# gatedriver_trafo_sma_compact_ACDC_ultra.net
KiCad netlist of a schematic drawn in EAGLE
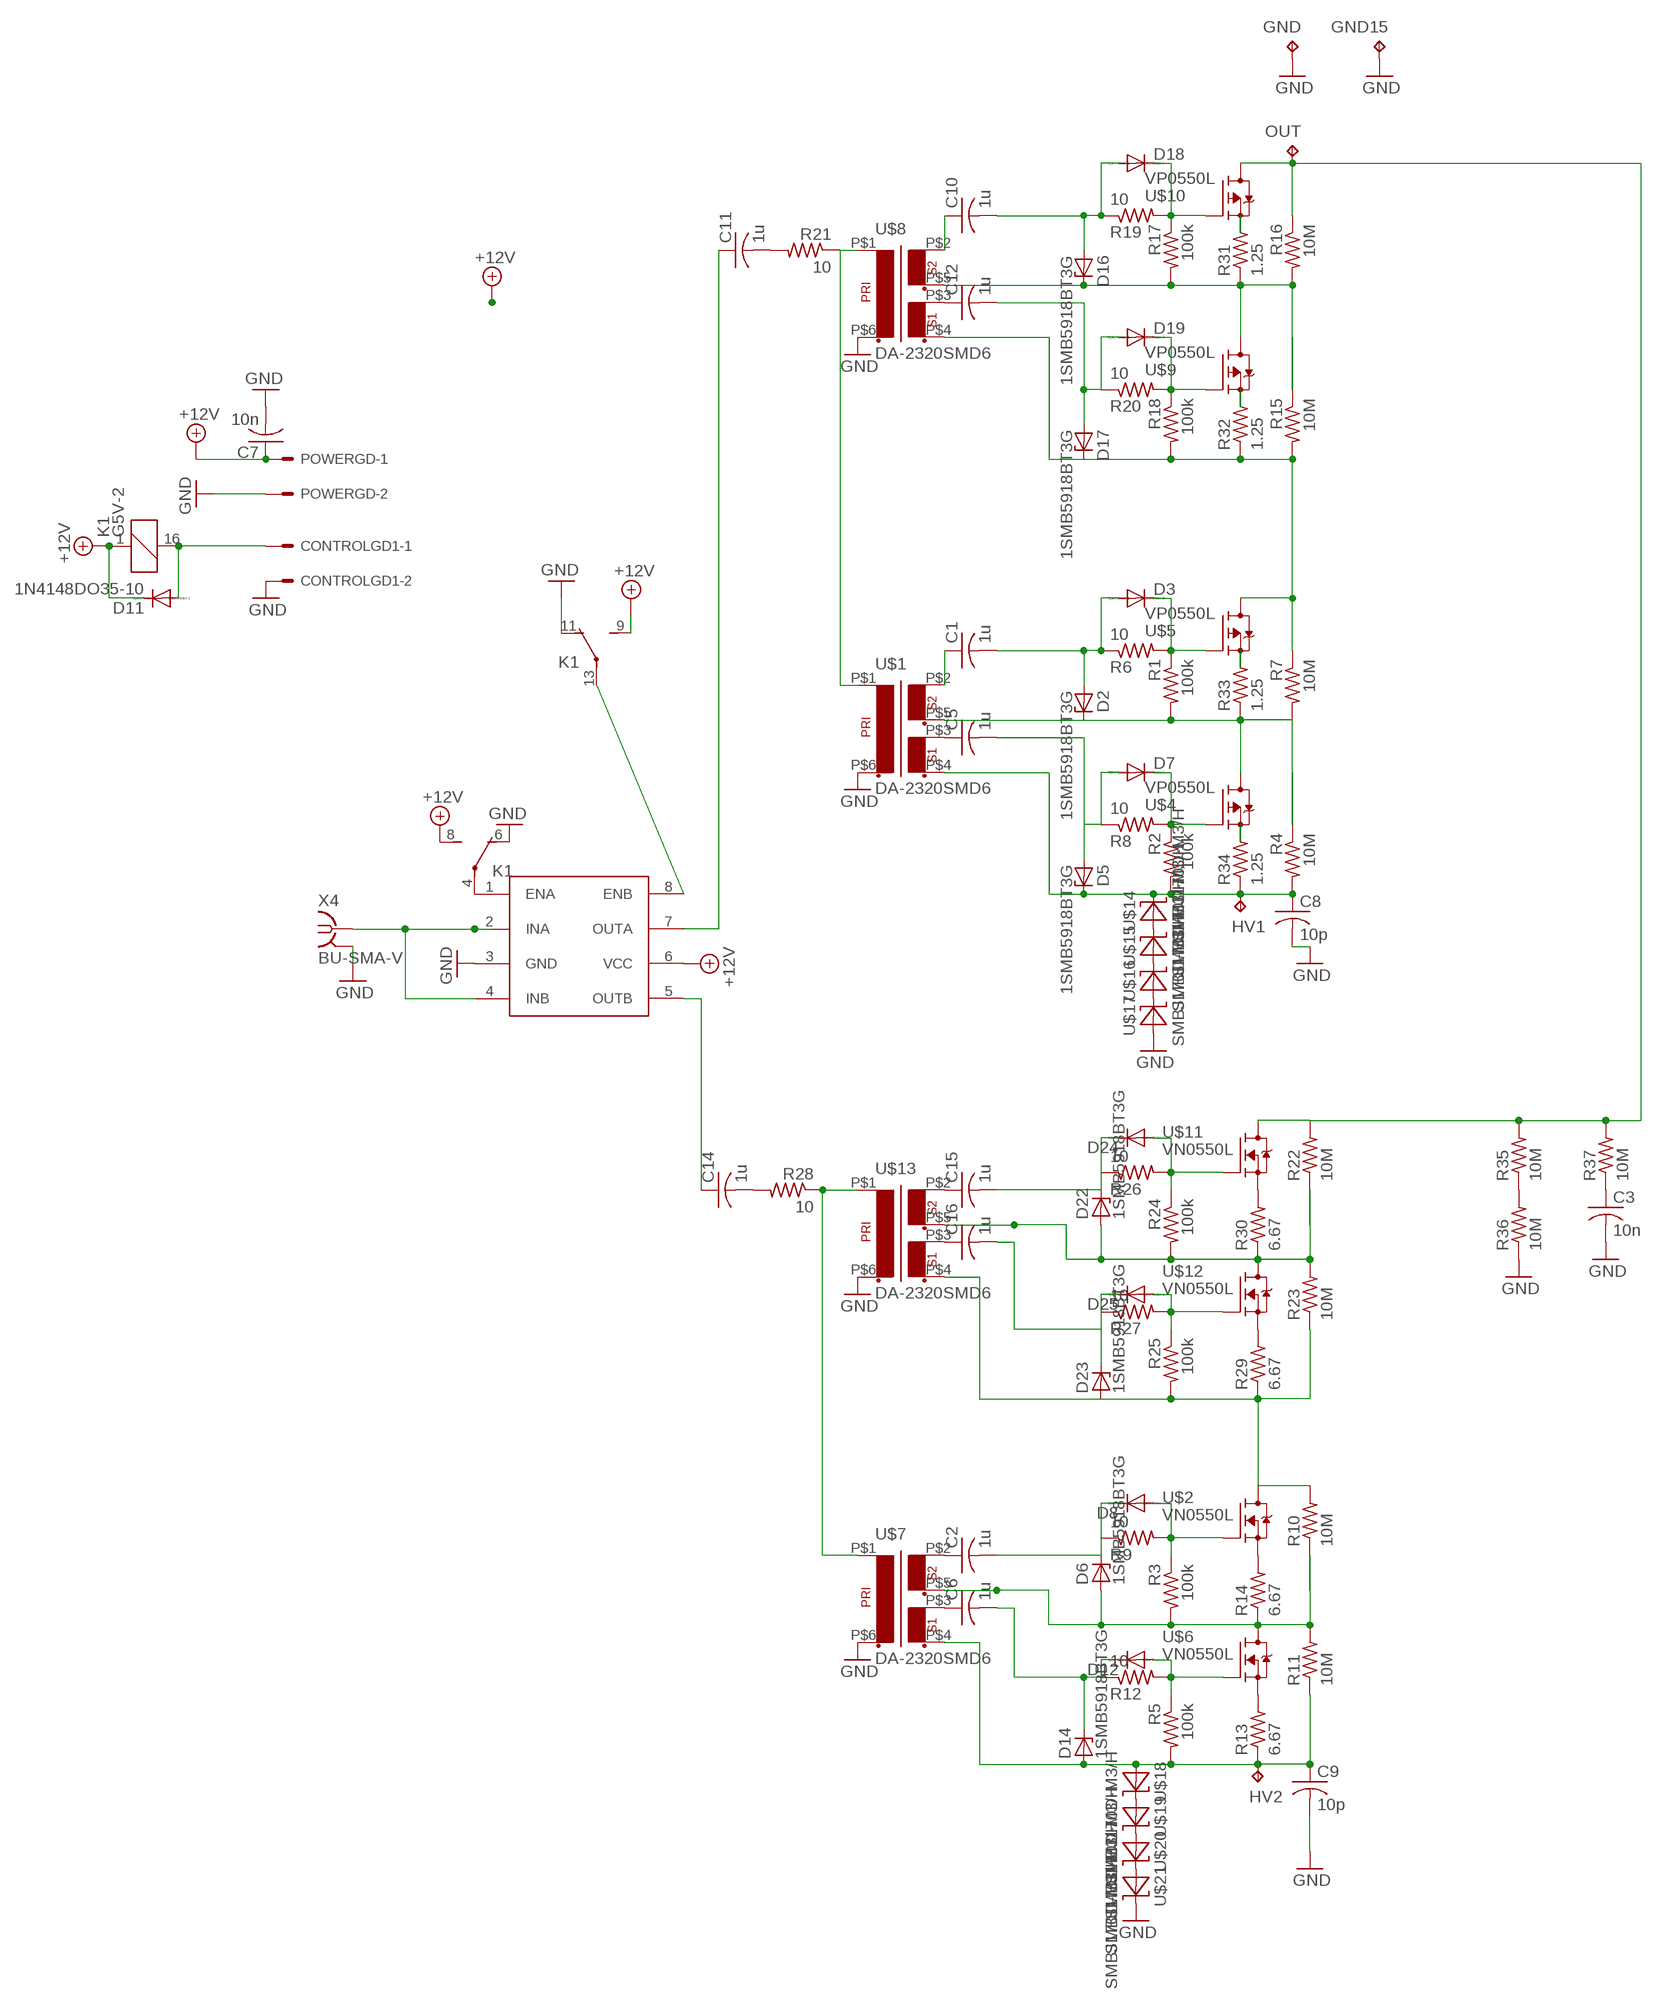
[diagram p0: schematic, sheet 1]

(export (version "E")
  (design (tool "Eeschema 10.0.6"))
  (components
    (comp (ref "C1")
      (value "1u")
      (footprint "eagle-import:C0805")
      (libsource (lib "eagle-import") (part "resistor_C-USC0805"))
    )
    (comp (ref "C2")
      (value "1u")
      (footprint "eagle-import:C0805")
      (libsource (lib "eagle-import") (part "resistor_C-USC0805"))
    )
    (comp (ref "C3")
      (value "10n")
      (footprint "eagle-import:C0805")
      (libsource (lib "eagle-import") (part "resistor_C-USC0805"))
    )
    (comp (ref "C5")
      (value "1u")
      (footprint "eagle-import:C0805")
      (libsource (lib "eagle-import") (part "resistor_C-USC0805"))
    )
    (comp (ref "C6")
      (value "1u")
      (footprint "eagle-import:C0805")
      (libsource (lib "eagle-import") (part "resistor_C-USC0805"))
    )
    (comp (ref "C7")
      (value "10n")
      (footprint "eagle-import:C050-030X075")
      (libsource (lib "eagle-import") (part "C-US050-030X075"))
    )
    (comp (ref "C8")
      (value "10p")
      (footprint "eagle-import:C102-064X133")
      (libsource (lib "eagle-import") (part "resistor_C-US102-064X133"))
    )
    (comp (ref "C9")
      (value "10p")
      (footprint "eagle-import:C102-064X133")
      (libsource (lib "eagle-import") (part "resistor_C-US102-064X133"))
    )
    (comp (ref "C10")
      (value "1u")
      (footprint "eagle-import:C0805")
      (libsource (lib "eagle-import") (part "resistor_C-USC0805"))
    )
    (comp (ref "C11")
      (value "1u")
      (footprint "eagle-import:C0805")
      (libsource (lib "eagle-import") (part "resistor_C-USC0805"))
    )
    (comp (ref "C12")
      (value "1u")
      (footprint "eagle-import:C0805")
      (libsource (lib "eagle-import") (part "resistor_C-USC0805"))
    )
    (comp (ref "C14")
      (value "1u")
      (footprint "eagle-import:C0805")
      (libsource (lib "eagle-import") (part "resistor_C-USC0805"))
    )
    (comp (ref "C15")
      (value "1u")
      (footprint "eagle-import:C0805")
      (libsource (lib "eagle-import") (part "resistor_C-USC0805"))
    )
    (comp (ref "C16")
      (value "1u")
      (footprint "eagle-import:C0805")
      (libsource (lib "eagle-import") (part "resistor_C-USC0805"))
    )
    (comp (ref "CONTROLGD1")
      (value "KK-156-2")
      (footprint "eagle-import:KK-156-2")
      (libsource (lib "eagle-import") (part "KK-156-2"))
    )
    (comp (ref "D2")
      (value "1SMB5918BT3G")
      (footprint "eagle-import:SMB")
      (libsource (lib "eagle-import") (part "ZENER-DIODESMB"))
    )
    (comp (ref "D3")
      (value "DIODE-SMB")
      (footprint "eagle-import:SMB")
      (libsource (lib "eagle-import") (part "DIODE-SMB"))
    )
    (comp (ref "D5")
      (value "1SMB5918BT3G")
      (footprint "eagle-import:SMB")
      (libsource (lib "eagle-import") (part "ZENER-DIODESMB"))
    )
    (comp (ref "D6")
      (value "1SMB5918BT3G")
      (footprint "eagle-import:SMB")
      (libsource (lib "eagle-import") (part "ZENER-DIODESMB"))
    )
    (comp (ref "D7")
      (value "DIODE-SMB")
      (footprint "eagle-import:SMB")
      (libsource (lib "eagle-import") (part "DIODE-SMB"))
    )
    (comp (ref "D8")
      (value "DIODE-SMB")
      (footprint "eagle-import:SMB")
      (libsource (lib "eagle-import") (part "DIODE-SMB"))
    )
    (comp (ref "D11")
      (value "1N4148DO35-10")
      (footprint "eagle-import:DO35-10")
      (libsource (lib "eagle-import") (part "1N4148DO35-10"))
    )
    (comp (ref "D12")
      (value "DIODE-SMB")
      (footprint "eagle-import:SMB")
      (libsource (lib "eagle-import") (part "DIODE-SMB"))
    )
    (comp (ref "D14")
      (value "1SMB5918BT3G")
      (footprint "eagle-import:SMB")
      (libsource (lib "eagle-import") (part "ZENER-DIODESMB"))
    )
    (comp (ref "D16")
      (value "1SMB5918BT3G")
      (footprint "eagle-import:SMB")
      (libsource (lib "eagle-import") (part "ZENER-DIODESMB"))
    )
    (comp (ref "D17")
      (value "1SMB5918BT3G")
      (footprint "eagle-import:SMB")
      (libsource (lib "eagle-import") (part "ZENER-DIODESMB"))
    )
    (comp (ref "D18")
      (value "DIODE-SMB")
      (footprint "eagle-import:SMB")
      (libsource (lib "eagle-import") (part "DIODE-SMB"))
    )
    (comp (ref "D19")
      (value "DIODE-SMB")
      (footprint "eagle-import:SMB")
      (libsource (lib "eagle-import") (part "DIODE-SMB"))
    )
    (comp (ref "D22")
      (value "1SMB5918BT3G")
      (footprint "eagle-import:SMB")
      (libsource (lib "eagle-import") (part "ZENER-DIODESMB"))
    )
    (comp (ref "D23")
      (value "1SMB5918BT3G")
      (footprint "eagle-import:SMB")
      (libsource (lib "eagle-import") (part "ZENER-DIODESMB"))
    )
    (comp (ref "D24")
      (value "DIODE-SMB")
      (footprint "eagle-import:SMB")
      (libsource (lib "eagle-import") (part "DIODE-SMB"))
    )
    (comp (ref "D25")
      (value "DIODE-SMB")
      (footprint "eagle-import:SMB")
      (libsource (lib "eagle-import") (part "DIODE-SMB"))
    )
    (comp (ref "GND")
      (value "TPPAD1-20Y")
      (footprint "eagle-import:P1-20Y")
      (libsource (lib "eagle-import") (part "TPPAD1-20Y"))
    )
    (comp (ref "GND15")
      (value "TPPAD1-20Y")
      (footprint "eagle-import:P1-20Y")
      (libsource (lib "eagle-import") (part "TPPAD1-20Y"))
    )
    (comp (ref "HV1")
      (value "TPPAD1-20Y")
      (footprint "eagle-import:P1-20Y")
      (libsource (lib "eagle-import") (part "TPPAD1-20Y"))
    )
    (comp (ref "HV2")
      (value "TPPAD1-20Y")
      (footprint "eagle-import:P1-20Y")
      (libsource (lib "eagle-import") (part "TPPAD1-20Y"))
    )
    (comp (ref "K1")
      (value "G5V-2")
      (footprint "eagle-import:G5V-2")
      (fields (field (name "MPN") "G5V-2 5DC"))
      (libsource (lib "eagle-import") (part "G5V-2"))
    )
    (comp (ref "OUT")
      (value "TPPAD1-20Y")
      (footprint "eagle-import:P1-20Y")
      (libsource (lib "eagle-import") (part "TPPAD1-20Y"))
    )
    (comp (ref "POWERGD")
      (value "KK-156-2")
      (footprint "eagle-import:KK-156-2")
      (libsource (lib "eagle-import") (part "KK-156-2"))
    )
    (comp (ref "R1")
      (value "100k")
      (footprint "eagle-import:R0805")
      (libsource (lib "eagle-import") (part "R-US_R0805"))
    )
    (comp (ref "R2")
      (value "100k")
      (footprint "eagle-import:R0805")
      (libsource (lib "eagle-import") (part "R-US_R0805"))
    )
    (comp (ref "R3")
      (value "100k")
      (footprint "eagle-import:R0805")
      (libsource (lib "eagle-import") (part "R-US_R0805"))
    )
    (comp (ref "R4")
      (value "10M")
      (footprint "eagle-import:R2512")
      (libsource (lib "eagle-import") (part "R-US_R2512"))
    )
    (comp (ref "R5")
      (value "100k")
      (footprint "eagle-import:R0805")
      (libsource (lib "eagle-import") (part "R-US_R0805"))
    )
    (comp (ref "R6")
      (value "10")
      (footprint "eagle-import:R0805")
      (libsource (lib "eagle-import") (part "R-US_R0805"))
    )
    (comp (ref "R7")
      (value "10M")
      (footprint "eagle-import:R2512")
      (libsource (lib "eagle-import") (part "R-US_R2512"))
    )
    (comp (ref "R8")
      (value "10")
      (footprint "eagle-import:R0805")
      (libsource (lib "eagle-import") (part "R-US_R0805"))
    )
    (comp (ref "R9")
      (value "10")
      (footprint "eagle-import:R0805")
      (libsource (lib "eagle-import") (part "R-US_R0805"))
    )
    (comp (ref "R10")
      (value "10M")
      (footprint "eagle-import:R2512")
      (libsource (lib "eagle-import") (part "R-US_R2512"))
    )
    (comp (ref "R11")
      (value "10M")
      (footprint "eagle-import:R2512")
      (libsource (lib "eagle-import") (part "R-US_R2512"))
    )
    (comp (ref "R12")
      (value "10")
      (footprint "eagle-import:R0805")
      (libsource (lib "eagle-import") (part "R-US_R0805"))
    )
    (comp (ref "R13")
      (value "6.67")
      (footprint "eagle-import:R0805")
      (libsource (lib "eagle-import") (part "R-US_R0805"))
    )
    (comp (ref "R14")
      (value "6.67")
      (footprint "eagle-import:R0805")
      (libsource (lib "eagle-import") (part "R-US_R0805"))
    )
    (comp (ref "R15")
      (value "10M")
      (footprint "eagle-import:R2512")
      (libsource (lib "eagle-import") (part "R-US_R2512"))
    )
    (comp (ref "R16")
      (value "10M")
      (footprint "eagle-import:R2512")
      (libsource (lib "eagle-import") (part "R-US_R2512"))
    )
    (comp (ref "R17")
      (value "100k")
      (footprint "eagle-import:R0805")
      (libsource (lib "eagle-import") (part "R-US_R0805"))
    )
    (comp (ref "R18")
      (value "100k")
      (footprint "eagle-import:R0805")
      (libsource (lib "eagle-import") (part "R-US_R0805"))
    )
    (comp (ref "R19")
      (value "10")
      (footprint "eagle-import:R0805")
      (libsource (lib "eagle-import") (part "R-US_R0805"))
    )
    (comp (ref "R20")
      (value "10")
      (footprint "eagle-import:R0805")
      (libsource (lib "eagle-import") (part "R-US_R0805"))
    )
    (comp (ref "R21")
      (value "10")
      (footprint "eagle-import:R0805")
      (libsource (lib "eagle-import") (part "R-US_R0805"))
    )
    (comp (ref "R22")
      (value "10M")
      (footprint "eagle-import:R2512")
      (libsource (lib "eagle-import") (part "R-US_R2512"))
    )
    (comp (ref "R23")
      (value "10M")
      (footprint "eagle-import:R2512")
      (libsource (lib "eagle-import") (part "R-US_R2512"))
    )
    (comp (ref "R24")
      (value "100k")
      (footprint "eagle-import:R0805")
      (libsource (lib "eagle-import") (part "R-US_R0805"))
    )
    (comp (ref "R25")
      (value "100k")
      (footprint "eagle-import:R0805")
      (libsource (lib "eagle-import") (part "R-US_R0805"))
    )
    (comp (ref "R26")
      (value "10")
      (footprint "eagle-import:R0805")
      (libsource (lib "eagle-import") (part "R-US_R0805"))
    )
    (comp (ref "R27")
      (value "10")
      (footprint "eagle-import:R0805")
      (libsource (lib "eagle-import") (part "R-US_R0805"))
    )
    (comp (ref "R28")
      (value "10")
      (footprint "eagle-import:R0805")
      (libsource (lib "eagle-import") (part "R-US_R0805"))
    )
    (comp (ref "R29")
      (value "6.67")
      (footprint "eagle-import:R0805")
      (libsource (lib "eagle-import") (part "R-US_R0805"))
    )
    (comp (ref "R30")
      (value "6.67")
      (footprint "eagle-import:R0805")
      (libsource (lib "eagle-import") (part "R-US_R0805"))
    )
    (comp (ref "R31")
      (value "1.25")
      (footprint "eagle-import:R0805")
      (libsource (lib "eagle-import") (part "R-US_R0805"))
    )
    (comp (ref "R32")
      (value "1.25")
      (footprint "eagle-import:R0805")
      (libsource (lib "eagle-import") (part "R-US_R0805"))
    )
    (comp (ref "R33")
      (value "1.25")
      (footprint "eagle-import:R0805")
      (libsource (lib "eagle-import") (part "R-US_R0805"))
    )
    (comp (ref "R34")
      (value "1.25")
      (footprint "eagle-import:R0805")
      (libsource (lib "eagle-import") (part "R-US_R0805"))
    )
    (comp (ref "R35")
      (value "10M")
      (footprint "eagle-import:R2512")
      (libsource (lib "eagle-import") (part "R-US_R2512"))
    )
    (comp (ref "R36")
      (value "10M")
      (footprint "eagle-import:R2512")
      (libsource (lib "eagle-import") (part "R-US_R2512"))
    )
    (comp (ref "R37")
      (value "10M")
      (footprint "eagle-import:R2512")
      (libsource (lib "eagle-import") (part "R-US_R2512"))
    )
    (comp (ref "U$1")
      (value "DA-2320SMD6")
      (footprint "eagle-import:SMD6")
      (libsource (lib "eagle-import") (part "DA-2320SMD6"))
    )
    (comp (ref "U$2")
      (value "VN0550L")
      (footprint "eagle-import:TO92L")
      (libsource (lib "eagle-import") (part "VN0550L"))
    )
    (comp (ref "U$3")
      (value "UCC27425")
      (footprint "eagle-import:DIL08")
      (libsource (lib "eagle-import") (part "UCC27425"))
    )
    (comp (ref "U$4")
      (value "VP0550L")
      (footprint "eagle-import:TO92L")
      (libsource (lib "eagle-import") (part "VP0550L"))
    )
    (comp (ref "U$5")
      (value "VP0550L")
      (footprint "eagle-import:TO92L")
      (libsource (lib "eagle-import") (part "VP0550L"))
    )
    (comp (ref "U$6")
      (value "VN0550L")
      (footprint "eagle-import:TO92L")
      (libsource (lib "eagle-import") (part "VN0550L"))
    )
    (comp (ref "U$7")
      (value "DA-2320SMD6")
      (footprint "eagle-import:SMD6")
      (libsource (lib "eagle-import") (part "DA-2320SMD6"))
    )
    (comp (ref "U$8")
      (value "DA-2320SMD6")
      (footprint "eagle-import:SMD6")
      (libsource (lib "eagle-import") (part "DA-2320SMD6"))
    )
    (comp (ref "U$9")
      (value "VP0550L")
      (footprint "eagle-import:TO92L")
      (libsource (lib "eagle-import") (part "VP0550L"))
    )
    (comp (ref "U$10")
      (value "VP0550L")
      (footprint "eagle-import:TO92L")
      (libsource (lib "eagle-import") (part "VP0550L"))
    )
    (comp (ref "U$11")
      (value "VN0550L")
      (footprint "eagle-import:TO92L")
      (libsource (lib "eagle-import") (part "VN0550L"))
    )
    (comp (ref "U$12")
      (value "VN0550L")
      (footprint "eagle-import:TO92L")
      (libsource (lib "eagle-import") (part "VN0550L"))
    )
    (comp (ref "U$13")
      (value "DA-2320SMD6")
      (footprint "eagle-import:SMD6")
      (libsource (lib "eagle-import") (part "DA-2320SMD6"))
    )
    (comp (ref "U$14")
      (value "SMBJ170D-M3/H")
      (footprint "eagle-import:DO214AA")
      (libsource (lib "eagle-import") (part "SMBJ170D-M3/H"))
    )
    (comp (ref "U$15")
      (value "SMBJ170D-M3/H")
      (footprint "eagle-import:DO214AA")
      (libsource (lib "eagle-import") (part "SMBJ170D-M3/H"))
    )
    (comp (ref "U$16")
      (value "SMBJ170D-M3/H")
      (footprint "eagle-import:DO214AA")
      (libsource (lib "eagle-import") (part "SMBJ170D-M3/H"))
    )
    (comp (ref "U$17")
      (value "SMBJ170D-M3/H")
      (footprint "eagle-import:DO214AA")
      (libsource (lib "eagle-import") (part "SMBJ170D-M3/H"))
    )
    (comp (ref "U$18")
      (value "SMBJ170D-M3/H")
      (footprint "eagle-import:DO214AA")
      (libsource (lib "eagle-import") (part "SMBJ170D-M3/H"))
    )
    (comp (ref "U$19")
      (value "SMBJ170D-M3/H")
      (footprint "eagle-import:DO214AA")
      (libsource (lib "eagle-import") (part "SMBJ170D-M3/H"))
    )
    (comp (ref "U$20")
      (value "SMBJ170D-M3/H")
      (footprint "eagle-import:DO214AA")
      (libsource (lib "eagle-import") (part "SMBJ170D-M3/H"))
    )
    (comp (ref "U$21")
      (value "SMBJ170D-M3/H")
      (footprint "eagle-import:DO214AA")
      (libsource (lib "eagle-import") (part "SMBJ170D-M3/H"))
    )
    (comp (ref "X4")
      (value "BU-SMA-V")
      (footprint "eagle-import:BU-SMA-V")
      (libsource (lib "eagle-import") (part "BU-SMA-V"))
    )
  )
  (nets
    (net (code "1") (name "+12V") (class "Default")
      (node (ref "C7") (pin "1") (pinfunction "1_1") (pintype "passive"))
      (node (ref "D11") (pin "C") (pinfunction "C_C") (pintype "passive"))
      (node (ref "K1") (pin "1") (pinfunction "1_1") (pintype "passive"))
      (node (ref "K1") (pin "8") (pinfunction "S_8") (pintype "passive"))
      (node (ref "K1") (pin "9") (pinfunction "S_9") (pintype "passive"))
      (node (ref "POWERGD") (pin "1") (pinfunction "S_1") (pintype "passive"))
      (node (ref "U$3") (pin "6") (pinfunction "VCC_6") (pintype "bidirectional"))
    )
    (net (code "2") (name "GND") (class "Default")
      (node (ref "C3") (pin "2") (pinfunction "2_2") (pintype "passive"))
      (node (ref "C7") (pin "2") (pinfunction "2_2") (pintype "passive"))
      (node (ref "C8") (pin "2") (pinfunction "2_2") (pintype "passive"))
      (node (ref "C9") (pin "2") (pinfunction "2_2") (pintype "passive"))
      (node (ref "CONTROLGD1") (pin "2") (pinfunction "S_2") (pintype "passive"))
      (node (ref "GND") (pin "TP") (pinfunction "TP_TP") (pintype "input"))
      (node (ref "GND15") (pin "TP") (pinfunction "TP_TP") (pintype "input"))
      (node (ref "K1") (pin "11") (pinfunction "O_11") (pintype "passive"))
      (node (ref "K1") (pin "6") (pinfunction "O_6") (pintype "passive"))
      (node (ref "POWERGD") (pin "2") (pinfunction "S_2") (pintype "passive"))
      (node (ref "R36") (pin "1") (pinfunction "1_1") (pintype "passive"))
      (node (ref "U$1") (pin "P$6") (pinfunction "2_P$6") (pintype "passive"))
      (node (ref "U$13") (pin "P$6") (pinfunction "2_P$6") (pintype "passive"))
      (node (ref "U$17") (pin "A") (pinfunction "A_A") (pintype "passive"))
      (node (ref "U$21") (pin "C") (pinfunction "C_C") (pintype "passive"))
      (node (ref "U$3") (pin "3") (pinfunction "GND_3") (pintype "bidirectional"))
      (node (ref "U$7") (pin "P$6") (pinfunction "2_P$6") (pintype "passive"))
      (node (ref "U$8") (pin "P$6") (pinfunction "2_P$6") (pintype "passive"))
      (node (ref "X4") (pin "2") (pinfunction "2_2") (pintype "passive"))
      (node (ref "X4") (pin "3") (pinfunction "2_3") (pintype "passive"))
      (node (ref "X4") (pin "4") (pinfunction "2_4") (pintype "passive"))
      (node (ref "X4") (pin "5") (pinfunction "2_5") (pintype "passive"))
    )
    (net (code "3") (name "Net-(C1-Pad2)") (class "Default")
      (node (ref "C1") (pin "2") (pinfunction "2_2") (pintype "passive"))
      (node (ref "D2") (pin "A") (pinfunction "A_A") (pintype "passive"))
      (node (ref "D3") (pin "A") (pinfunction "A_A") (pintype "passive"))
      (node (ref "R6") (pin "1") (pinfunction "1_1") (pintype "passive"))
    )
    (net (code "4") (name "Net-(C2-Pad2)") (class "Default")
      (node (ref "C2") (pin "2") (pinfunction "2_2") (pintype "passive"))
      (node (ref "D6") (pin "C") (pinfunction "C_C") (pintype "passive"))
      (node (ref "D8") (pin "C") (pinfunction "C_C") (pintype "passive"))
      (node (ref "R9") (pin "1") (pinfunction "1_1") (pintype "passive"))
    )
    (net (code "5") (name "Net-(C3-Pad1)") (class "Default")
      (node (ref "C3") (pin "1") (pinfunction "1_1") (pintype "passive"))
      (node (ref "R37") (pin "1") (pinfunction "1_1") (pintype "passive"))
    )
    (net (code "6") (name "Net-(C5-Pad2)") (class "Default")
      (node (ref "C5") (pin "2") (pinfunction "2_2") (pintype "passive"))
      (node (ref "D5") (pin "A") (pinfunction "A_A") (pintype "passive"))
      (node (ref "D7") (pin "A") (pinfunction "A_A") (pintype "passive"))
      (node (ref "R8") (pin "1") (pinfunction "1_1") (pintype "passive"))
    )
    (net (code "7") (name "Net-(C6-Pad2)") (class "Default")
      (node (ref "C6") (pin "2") (pinfunction "2_2") (pintype "passive"))
      (node (ref "D12") (pin "C") (pinfunction "C_C") (pintype "passive"))
      (node (ref "D14") (pin "C") (pinfunction "C_C") (pintype "passive"))
      (node (ref "R12") (pin "1") (pinfunction "1_1") (pintype "passive"))
    )
    (net (code "8") (name "Net-(C10-Pad2)") (class "Default")
      (node (ref "C10") (pin "2") (pinfunction "2_2") (pintype "passive"))
      (node (ref "D16") (pin "A") (pinfunction "A_A") (pintype "passive"))
      (node (ref "D18") (pin "A") (pinfunction "A_A") (pintype "passive"))
      (node (ref "R19") (pin "1") (pinfunction "1_1") (pintype "passive"))
    )
    (net (code "9") (name "Net-(C11-Pad2)") (class "Default")
      (node (ref "C11") (pin "2") (pinfunction "2_2") (pintype "passive"))
      (node (ref "R21") (pin "2") (pinfunction "2_2") (pintype "passive"))
    )
    (net (code "10") (name "Net-(C12-Pad2)") (class "Default")
      (node (ref "C12") (pin "2") (pinfunction "2_2") (pintype "passive"))
      (node (ref "D17") (pin "A") (pinfunction "A_A") (pintype "passive"))
      (node (ref "D19") (pin "A") (pinfunction "A_A") (pintype "passive"))
      (node (ref "R20") (pin "1") (pinfunction "1_1") (pintype "passive"))
    )
    (net (code "11") (name "Net-(C14-Pad2)") (class "Default")
      (node (ref "C14") (pin "2") (pinfunction "2_2") (pintype "passive"))
      (node (ref "R28") (pin "2") (pinfunction "2_2") (pintype "passive"))
    )
    (net (code "12") (name "Net-(C15-Pad2)") (class "Default")
      (node (ref "C15") (pin "2") (pinfunction "2_2") (pintype "passive"))
      (node (ref "D22") (pin "C") (pinfunction "C_C") (pintype "passive"))
      (node (ref "D24") (pin "C") (pinfunction "C_C") (pintype "passive"))
      (node (ref "R26") (pin "1") (pinfunction "1_1") (pintype "passive"))
    )
    (net (code "13") (name "Net-(C16-Pad2)") (class "Default")
      (node (ref "C16") (pin "2") (pinfunction "2_2") (pintype "passive"))
      (node (ref "D23") (pin "C") (pinfunction "C_C") (pintype "passive"))
      (node (ref "D25") (pin "C") (pinfunction "C_C") (pintype "passive"))
      (node (ref "R27") (pin "1") (pinfunction "1_1") (pintype "passive"))
    )
    (net (code "14") (name "Net-(CONTROLGD1A-S)") (class "Default")
      (node (ref "CONTROLGD1") (pin "1") (pinfunction "S_1") (pintype "passive"))
      (node (ref "D11") (pin "A") (pinfunction "A_A") (pintype "passive"))
      (node (ref "K1") (pin "16") (pinfunction "2_16") (pintype "passive"))
    )
    (net (code "15") (name "Net-(K1A-P)") (class "Default")
      (node (ref "K1") (pin "4") (pinfunction "P_4") (pintype "passive"))
      (node (ref "U$3") (pin "1") (pinfunction "ENA_1") (pintype "bidirectional"))
    )
    (net (code "16") (name "Net-(K1B-P)") (class "Default")
      (node (ref "K1") (pin "13") (pinfunction "P_13") (pintype "passive"))
      (node (ref "U$3") (pin "8") (pinfunction "ENB_8") (pintype "bidirectional"))
    )
    (net (code "17") (name "Net-(R35-Pad1)") (class "Default")
      (node (ref "R35") (pin "1") (pinfunction "1_1") (pintype "passive"))
      (node (ref "R36") (pin "2") (pinfunction "2_2") (pintype "passive"))
    )
    (net (code "18") (name "Net-(U$1-1)") (class "Default")
      (node (ref "R21") (pin "1") (pinfunction "1_1") (pintype "passive"))
      (node (ref "U$1") (pin "P$1") (pinfunction "1_P$1") (pintype "passive"))
      (node (ref "U$8") (pin "P$1") (pinfunction "1_P$1") (pintype "passive"))
    )
    (net (code "19") (name "Net-(U$1-3)") (class "Default")
      (node (ref "C8") (pin "1") (pinfunction "1_1") (pintype "passive"))
      (node (ref "D5") (pin "C") (pinfunction "C_C") (pintype "passive"))
      (node (ref "HV1") (pin "TP") (pinfunction "TP_TP") (pintype "input"))
      (node (ref "R2") (pin "2") (pinfunction "2_2") (pintype "passive"))
      (node (ref "R34") (pin "1") (pinfunction "1_1") (pintype "passive"))
      (node (ref "R4") (pin "2") (pinfunction "2_2") (pintype "passive"))
      (node (ref "U$1") (pin "P$4") (pinfunction "3_P$4") (pintype "passive"))
      (node (ref "U$14") (pin "C") (pinfunction "C_C") (pintype "passive"))
    )
    (net (code "20") (name "Net-(U$1-4)") (class "Default")
      (node (ref "C5") (pin "1") (pinfunction "1_1") (pintype "passive"))
      (node (ref "U$1") (pin "P$3") (pinfunction "4_P$3") (pintype "passive"))
    )
    (net (code "21") (name "Net-(U$1-5)") (class "Default")
      (node (ref "D2") (pin "C") (pinfunction "C_C") (pintype "passive"))
      (node (ref "R1") (pin "2") (pinfunction "2_2") (pintype "passive"))
      (node (ref "R33") (pin "1") (pinfunction "1_1") (pintype "passive"))
      (node (ref "R4") (pin "1") (pinfunction "1_1") (pintype "passive"))
      (node (ref "R7") (pin "2") (pinfunction "2_2") (pintype "passive"))
      (node (ref "U$1") (pin "P$5") (pinfunction "5_P$5") (pintype "passive"))
      (node (ref "U$4") (pin "1") (pinfunction "D_1") (pintype "passive"))
    )
    (net (code "22") (name "Net-(U$1-6)") (class "Default")
      (node (ref "C1") (pin "1") (pinfunction "1_1") (pintype "passive"))
      (node (ref "U$1") (pin "P$2") (pinfunction "6_P$2") (pintype "passive"))
    )
    (net (code "23") (name "Net-(U$2-G)") (class "Default")
      (node (ref "D8") (pin "A") (pinfunction "A_A") (pintype "passive"))
      (node (ref "R3") (pin "1") (pinfunction "1_1") (pintype "passive"))
      (node (ref "R9") (pin "2") (pinfunction "2_2") (pintype "passive"))
      (node (ref "U$2") (pin "2") (pinfunction "G_2") (pintype "passive"))
    )
    (net (code "24") (name "Net-(U$2-S)") (class "Default")
      (node (ref "R14") (pin "2") (pinfunction "2_2") (pintype "passive"))
      (node (ref "U$2") (pin "3") (pinfunction "S_3") (pintype "passive"))
    )
    (net (code "25") (name "Net-(U$3-INA)") (class "Default")
      (node (ref "U$3") (pin "2") (pinfunction "INA_2") (pintype "bidirectional"))
      (node (ref "U$3") (pin "4") (pinfunction "INB_4") (pintype "bidirectional"))
      (node (ref "X4") (pin "1") (pinfunction "1_1") (pintype "passive"))
    )
    (net (code "26") (name "Net-(U$3-OUTA)") (class "Default")
      (node (ref "C11") (pin "1") (pinfunction "1_1") (pintype "passive"))
      (node (ref "U$3") (pin "7") (pinfunction "OUTA_7") (pintype "bidirectional"))
    )
    (net (code "27") (name "Net-(U$3-OUTB)") (class "Default")
      (node (ref "C14") (pin "1") (pinfunction "1_1") (pintype "passive"))
      (node (ref "U$3") (pin "5") (pinfunction "OUTB_5") (pintype "bidirectional"))
    )
    (net (code "28") (name "Net-(U$4-G)") (class "Default")
      (node (ref "D7") (pin "C") (pinfunction "C_C") (pintype "passive"))
      (node (ref "R2") (pin "1") (pinfunction "1_1") (pintype "passive"))
      (node (ref "R8") (pin "2") (pinfunction "2_2") (pintype "passive"))
      (node (ref "U$4") (pin "2") (pinfunction "G_2") (pintype "passive"))
    )
    (net (code "29") (name "Net-(U$4-S)") (class "Default")
      (node (ref "R34") (pin "2") (pinfunction "2_2") (pintype "passive"))
      (node (ref "U$4") (pin "3") (pinfunction "S_3") (pintype "passive"))
    )
    (net (code "30") (name "Net-(U$5-D)") (class "Default")
      (node (ref "D17") (pin "C") (pinfunction "C_C") (pintype "passive"))
      (node (ref "R15") (pin "2") (pinfunction "2_2") (pintype "passive"))
      (node (ref "R18") (pin "2") (pinfunction "2_2") (pintype "passive"))
      (node (ref "R32") (pin "1") (pinfunction "1_1") (pintype "passive"))
      (node (ref "R7") (pin "1") (pinfunction "1_1") (pintype "passive"))
      (node (ref "U$5") (pin "1") (pinfunction "D_1") (pintype "passive"))
      (node (ref "U$8") (pin "P$4") (pinfunction "3_P$4") (pintype "passive"))
    )
    (net (code "31") (name "Net-(U$5-G)") (class "Default")
      (node (ref "D3") (pin "C") (pinfunction "C_C") (pintype "passive"))
      (node (ref "R1") (pin "1") (pinfunction "1_1") (pintype "passive"))
      (node (ref "R6") (pin "2") (pinfunction "2_2") (pintype "passive"))
      (node (ref "U$5") (pin "2") (pinfunction "G_2") (pintype "passive"))
    )
    (net (code "32") (name "Net-(U$5-S)") (class "Default")
      (node (ref "R33") (pin "2") (pinfunction "2_2") (pintype "passive"))
      (node (ref "U$5") (pin "3") (pinfunction "S_3") (pintype "passive"))
    )
    (net (code "33") (name "Net-(U$6-D)") (class "Default")
      (node (ref "D6") (pin "A") (pinfunction "A_A") (pintype "passive"))
      (node (ref "R10") (pin "1") (pinfunction "1_1") (pintype "passive"))
      (node (ref "R11") (pin "2") (pinfunction "2_2") (pintype "passive"))
      (node (ref "R14") (pin "1") (pinfunction "1_1") (pintype "passive"))
      (node (ref "R3") (pin "2") (pinfunction "2_2") (pintype "passive"))
      (node (ref "U$6") (pin "1") (pinfunction "D_1") (pintype "passive"))
      (node (ref "U$7") (pin "P$5") (pinfunction "5_P$5") (pintype "passive"))
    )
    (net (code "34") (name "Net-(U$6-G)") (class "Default")
      (node (ref "D12") (pin "A") (pinfunction "A_A") (pintype "passive"))
      (node (ref "R12") (pin "2") (pinfunction "2_2") (pintype "passive"))
      (node (ref "R5") (pin "1") (pinfunction "1_1") (pintype "passive"))
      (node (ref "U$6") (pin "2") (pinfunction "G_2") (pintype "passive"))
    )
    (net (code "35") (name "Net-(U$6-S)") (class "Default")
      (node (ref "R13") (pin "2") (pinfunction "2_2") (pintype "passive"))
      (node (ref "U$6") (pin "3") (pinfunction "S_3") (pintype "passive"))
    )
    (net (code "36") (name "Net-(U$7-3)") (class "Default")
      (node (ref "C9") (pin "1") (pinfunction "1_1") (pintype "passive"))
      (node (ref "D14") (pin "A") (pinfunction "A_A") (pintype "passive"))
      (node (ref "HV2") (pin "TP") (pinfunction "TP_TP") (pintype "input"))
      (node (ref "R11") (pin "1") (pinfunction "1_1") (pintype "passive"))
      (node (ref "R13") (pin "1") (pinfunction "1_1") (pintype "passive"))
      (node (ref "R5") (pin "2") (pinfunction "2_2") (pintype "passive"))
      (node (ref "U$18") (pin "A") (pinfunction "A_A") (pintype "passive"))
      (node (ref "U$7") (pin "P$4") (pinfunction "3_P$4") (pintype "passive"))
    )
    (net (code "37") (name "Net-(U$7-4)") (class "Default")
      (node (ref "C6") (pin "1") (pinfunction "1_1") (pintype "passive"))
      (node (ref "U$7") (pin "P$3") (pinfunction "4_P$3") (pintype "passive"))
    )
    (net (code "38") (name "Net-(U$7-6)") (class "Default")
      (node (ref "C2") (pin "1") (pinfunction "1_1") (pintype "passive"))
      (node (ref "U$7") (pin "P$2") (pinfunction "6_P$2") (pintype "passive"))
    )
    (net (code "39") (name "Net-(U$8-4)") (class "Default")
      (node (ref "C12") (pin "1") (pinfunction "1_1") (pintype "passive"))
      (node (ref "U$8") (pin "P$3") (pinfunction "4_P$3") (pintype "passive"))
    )
    (net (code "40") (name "Net-(U$8-5)") (class "Default")
      (node (ref "D16") (pin "C") (pinfunction "C_C") (pintype "passive"))
      (node (ref "R15") (pin "1") (pinfunction "1_1") (pintype "passive"))
      (node (ref "R16") (pin "2") (pinfunction "2_2") (pintype "passive"))
      (node (ref "R17") (pin "2") (pinfunction "2_2") (pintype "passive"))
      (node (ref "R31") (pin "1") (pinfunction "1_1") (pintype "passive"))
      (node (ref "U$8") (pin "P$5") (pinfunction "5_P$5") (pintype "passive"))
      (node (ref "U$9") (pin "1") (pinfunction "D_1") (pintype "passive"))
    )
    (net (code "41") (name "Net-(U$8-6)") (class "Default")
      (node (ref "C10") (pin "1") (pinfunction "1_1") (pintype "passive"))
      (node (ref "U$8") (pin "P$2") (pinfunction "6_P$2") (pintype "passive"))
    )
    (net (code "42") (name "Net-(U$9-G)") (class "Default")
      (node (ref "D19") (pin "C") (pinfunction "C_C") (pintype "passive"))
      (node (ref "R18") (pin "1") (pinfunction "1_1") (pintype "passive"))
      (node (ref "R20") (pin "2") (pinfunction "2_2") (pintype "passive"))
      (node (ref "U$9") (pin "2") (pinfunction "G_2") (pintype "passive"))
    )
    (net (code "43") (name "Net-(U$9-S)") (class "Default")
      (node (ref "R32") (pin "2") (pinfunction "2_2") (pintype "passive"))
      (node (ref "U$9") (pin "3") (pinfunction "S_3") (pintype "passive"))
    )
    (net (code "44") (name "Net-(U$10-D)") (class "Default")
      (node (ref "OUT") (pin "TP") (pinfunction "TP_TP") (pintype "input"))
      (node (ref "R16") (pin "1") (pinfunction "1_1") (pintype "passive"))
      (node (ref "R22") (pin "2") (pinfunction "2_2") (pintype "passive"))
      (node (ref "R35") (pin "2") (pinfunction "2_2") (pintype "passive"))
      (node (ref "R37") (pin "2") (pinfunction "2_2") (pintype "passive"))
      (node (ref "U$10") (pin "1") (pinfunction "D_1") (pintype "passive"))
      (node (ref "U$11") (pin "1") (pinfunction "D_1") (pintype "passive"))
    )
    (net (code "45") (name "Net-(U$10-G)") (class "Default")
      (node (ref "D18") (pin "C") (pinfunction "C_C") (pintype "passive"))
      (node (ref "R17") (pin "1") (pinfunction "1_1") (pintype "passive"))
      (node (ref "R19") (pin "2") (pinfunction "2_2") (pintype "passive"))
      (node (ref "U$10") (pin "2") (pinfunction "G_2") (pintype "passive"))
    )
    (net (code "46") (name "Net-(U$10-S)") (class "Default")
      (node (ref "R31") (pin "2") (pinfunction "2_2") (pintype "passive"))
      (node (ref "U$10") (pin "3") (pinfunction "S_3") (pintype "passive"))
    )
    (net (code "47") (name "Net-(U$11-G)") (class "Default")
      (node (ref "D24") (pin "A") (pinfunction "A_A") (pintype "passive"))
      (node (ref "R24") (pin "1") (pinfunction "1_1") (pintype "passive"))
      (node (ref "R26") (pin "2") (pinfunction "2_2") (pintype "passive"))
      (node (ref "U$11") (pin "2") (pinfunction "G_2") (pintype "passive"))
    )
    (net (code "48") (name "Net-(U$11-S)") (class "Default")
      (node (ref "R30") (pin "2") (pinfunction "2_2") (pintype "passive"))
      (node (ref "U$11") (pin "3") (pinfunction "S_3") (pintype "passive"))
    )
    (net (code "49") (name "Net-(U$12-D)") (class "Default")
      (node (ref "D22") (pin "A") (pinfunction "A_A") (pintype "passive"))
      (node (ref "R22") (pin "1") (pinfunction "1_1") (pintype "passive"))
      (node (ref "R23") (pin "2") (pinfunction "2_2") (pintype "passive"))
      (node (ref "R24") (pin "2") (pinfunction "2_2") (pintype "passive"))
      (node (ref "R30") (pin "1") (pinfunction "1_1") (pintype "passive"))
      (node (ref "U$12") (pin "1") (pinfunction "D_1") (pintype "passive"))
      (node (ref "U$13") (pin "P$5") (pinfunction "5_P$5") (pintype "passive"))
    )
    (net (code "50") (name "Net-(U$12-G)") (class "Default")
      (node (ref "D25") (pin "A") (pinfunction "A_A") (pintype "passive"))
      (node (ref "R25") (pin "1") (pinfunction "1_1") (pintype "passive"))
      (node (ref "R27") (pin "2") (pinfunction "2_2") (pintype "passive"))
      (node (ref "U$12") (pin "2") (pinfunction "G_2") (pintype "passive"))
    )
    (net (code "51") (name "Net-(U$12-S)") (class "Default")
      (node (ref "R29") (pin "2") (pinfunction "2_2") (pintype "passive"))
      (node (ref "U$12") (pin "3") (pinfunction "S_3") (pintype "passive"))
    )
    (net (code "52") (name "Net-(U$13-1)") (class "Default")
      (node (ref "R28") (pin "1") (pinfunction "1_1") (pintype "passive"))
      (node (ref "U$13") (pin "P$1") (pinfunction "1_P$1") (pintype "passive"))
      (node (ref "U$7") (pin "P$1") (pinfunction "1_P$1") (pintype "passive"))
    )
    (net (code "53") (name "Net-(U$13-3)") (class "Default")
      (node (ref "D23") (pin "A") (pinfunction "A_A") (pintype "passive"))
      (node (ref "R10") (pin "2") (pinfunction "2_2") (pintype "passive"))
      (node (ref "R23") (pin "1") (pinfunction "1_1") (pintype "passive"))
      (node (ref "R25") (pin "2") (pinfunction "2_2") (pintype "passive"))
      (node (ref "R29") (pin "1") (pinfunction "1_1") (pintype "passive"))
      (node (ref "U$13") (pin "P$4") (pinfunction "3_P$4") (pintype "passive"))
      (node (ref "U$2") (pin "1") (pinfunction "D_1") (pintype "passive"))
    )
    (net (code "54") (name "Net-(U$13-4)") (class "Default")
      (node (ref "C16") (pin "1") (pinfunction "1_1") (pintype "passive"))
      (node (ref "U$13") (pin "P$3") (pinfunction "4_P$3") (pintype "passive"))
    )
    (net (code "55") (name "Net-(U$13-6)") (class "Default")
      (node (ref "C15") (pin "1") (pinfunction "1_1") (pintype "passive"))
      (node (ref "U$13") (pin "P$2") (pinfunction "6_P$2") (pintype "passive"))
    )
    (net (code "56") (name "Net-(U$14-PadA)") (class "Default")
      (node (ref "U$14") (pin "A") (pinfunction "A_A") (pintype "passive"))
      (node (ref "U$15") (pin "C") (pinfunction "C_C") (pintype "passive"))
    )
    (net (code "57") (name "Net-(U$15-PadA)") (class "Default")
      (node (ref "U$15") (pin "A") (pinfunction "A_A") (pintype "passive"))
      (node (ref "U$16") (pin "C") (pinfunction "C_C") (pintype "passive"))
    )
    (net (code "58") (name "Net-(U$16-PadA)") (class "Default")
      (node (ref "U$16") (pin "A") (pinfunction "A_A") (pintype "passive"))
      (node (ref "U$17") (pin "C") (pinfunction "C_C") (pintype "passive"))
    )
    (net (code "59") (name "Net-(U$18-PadC)") (class "Default")
      (node (ref "U$18") (pin "C") (pinfunction "C_C") (pintype "passive"))
      (node (ref "U$19") (pin "A") (pinfunction "A_A") (pintype "passive"))
    )
    (net (code "60") (name "Net-(U$19-PadC)") (class "Default")
      (node (ref "U$19") (pin "C") (pinfunction "C_C") (pintype "passive"))
      (node (ref "U$20") (pin "A") (pinfunction "A_A") (pintype "passive"))
    )
    (net (code "61") (name "Net-(U$20-PadC)") (class "Default")
      (node (ref "U$20") (pin "C") (pinfunction "C_C") (pintype "passive"))
      (node (ref "U$21") (pin "A") (pinfunction "A_A") (pintype "passive"))
    )
  )
)
